# EMGPreamp_extRefv3.net
KiCad netlist of a schematic drawn in EAGLE
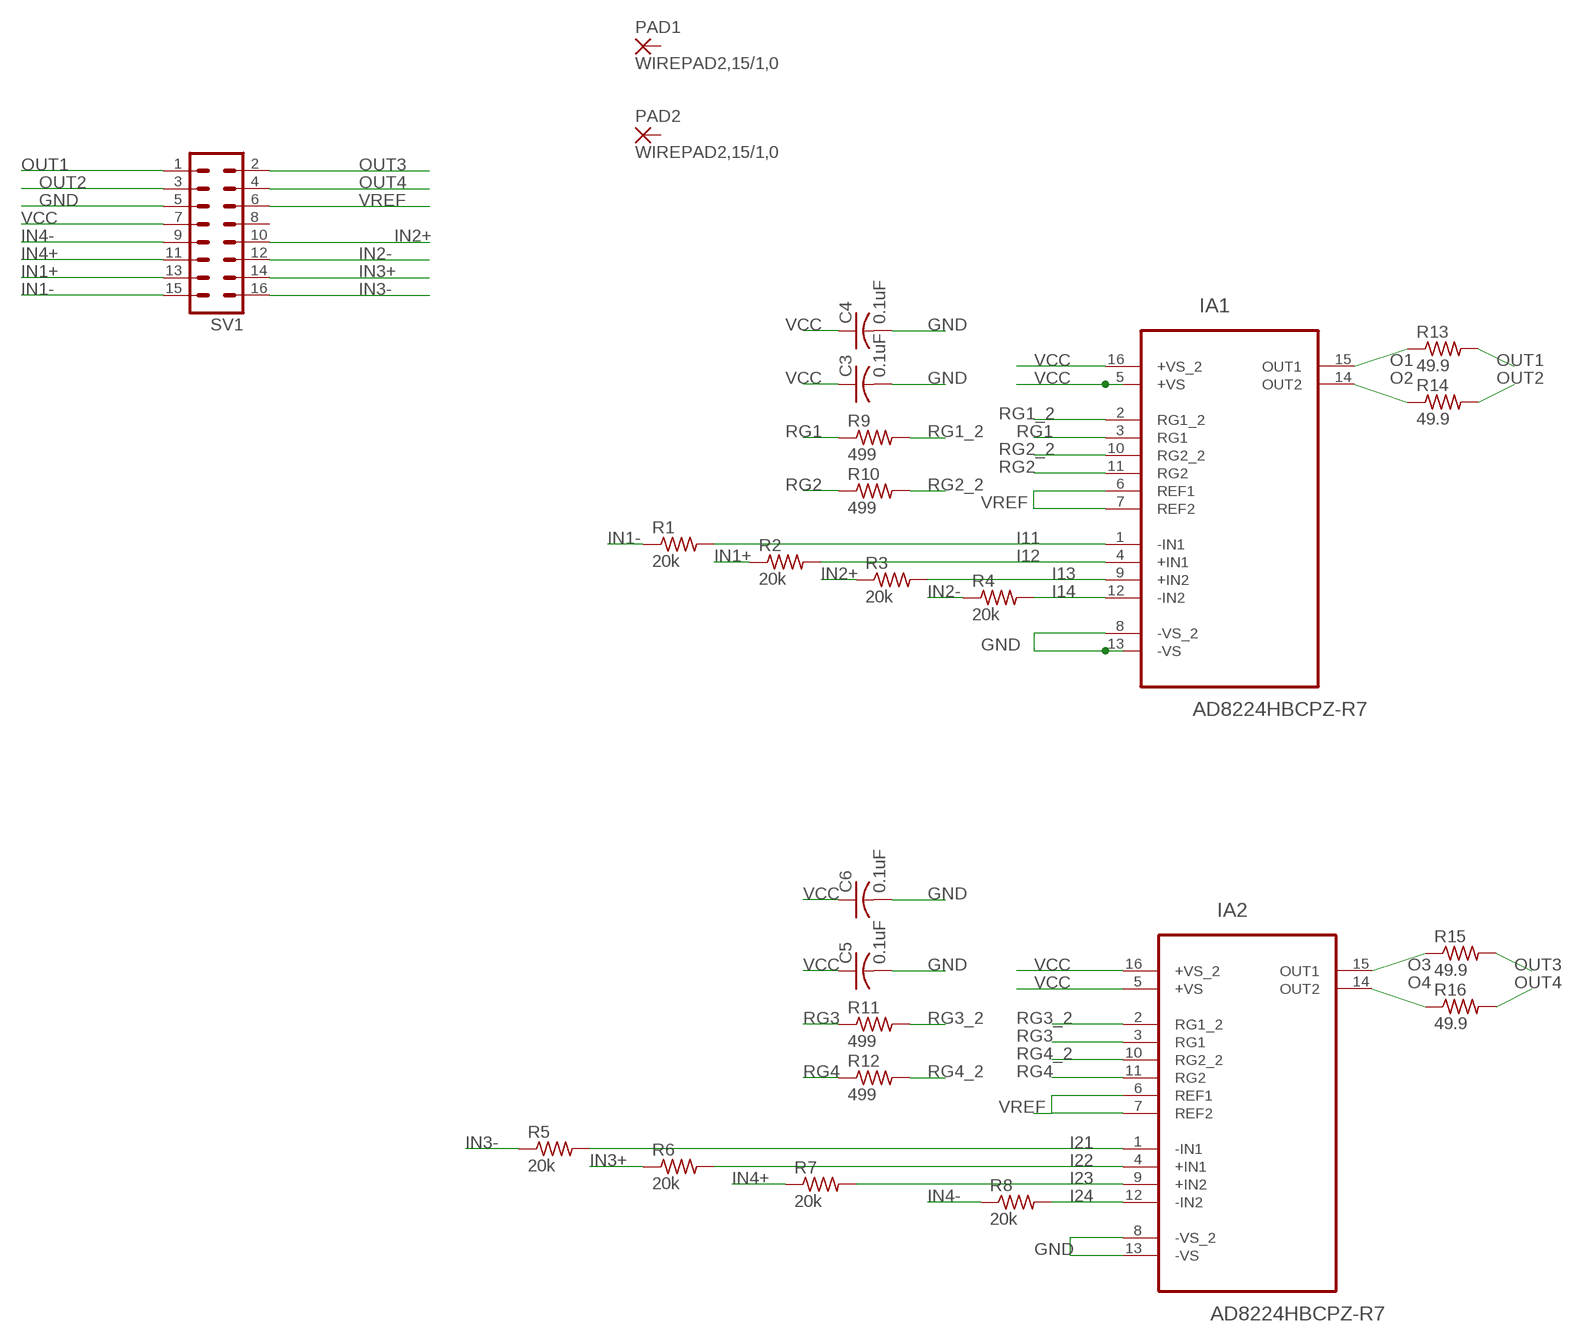
[diagram p0: schematic, sheet 1]

(export (version "E")
  (design (tool "Eeschema 10.0.6"))
  (components
    (comp (ref "C3")
      (value "0.1uF")
      (footprint "eagle-import:C0805")
      (libsource (lib "eagle-import") (part "C-USC0805"))
    )
    (comp (ref "C4")
      (value "0.1uF")
      (footprint "eagle-import:C0805")
      (libsource (lib "eagle-import") (part "C-USC0805"))
    )
    (comp (ref "C5")
      (value "0.1uF")
      (footprint "eagle-import:C0805")
      (libsource (lib "eagle-import") (part "C-USC0805"))
    )
    (comp (ref "C6")
      (value "0.1uF")
      (footprint "eagle-import:C0805")
      (libsource (lib "eagle-import") (part "C-USC0805"))
    )
    (comp (ref "IA1")
      (value "AD8224HBCPZ-R7")
      (footprint "eagle-import:QFN65P400X400X100-16N")
      (libsource (lib "eagle-import") (part "AD8224HBCPZ-R7"))
    )
    (comp (ref "IA2")
      (value "AD8224HBCPZ-R7")
      (footprint "eagle-import:QFN65P400X400X100-16N")
      (libsource (lib "eagle-import") (part "AD8224HBCPZ-R7"))
    )
    (comp (ref "PAD1")
      (value "WIREPAD2,15/1,0")
      (footprint "eagle-import:2,15_1,0")
      (libsource (lib "eagle-import") (part "WIREPAD2,15/1,0"))
    )
    (comp (ref "PAD2")
      (value "WIREPAD2,15/1,0")
      (footprint "eagle-import:2,15_1,0")
      (libsource (lib "eagle-import") (part "WIREPAD2,15/1,0"))
    )
    (comp (ref "R1")
      (value "20k")
      (footprint "eagle-import:R0805")
      (libsource (lib "eagle-import") (part "R-US_R0805"))
    )
    (comp (ref "R2")
      (value "20k")
      (footprint "eagle-import:R0805")
      (libsource (lib "eagle-import") (part "R-US_R0805"))
    )
    (comp (ref "R3")
      (value "20k")
      (footprint "eagle-import:R0805")
      (libsource (lib "eagle-import") (part "R-US_R0805"))
    )
    (comp (ref "R4")
      (value "20k")
      (footprint "eagle-import:R0805")
      (libsource (lib "eagle-import") (part "R-US_R0805"))
    )
    (comp (ref "R5")
      (value "20k")
      (footprint "eagle-import:R0805")
      (libsource (lib "eagle-import") (part "R-US_R0805"))
    )
    (comp (ref "R6")
      (value "20k")
      (footprint "eagle-import:R0805")
      (libsource (lib "eagle-import") (part "R-US_R0805"))
    )
    (comp (ref "R7")
      (value "20k")
      (footprint "eagle-import:R0805")
      (libsource (lib "eagle-import") (part "R-US_R0805"))
    )
    (comp (ref "R8")
      (value "20k")
      (footprint "eagle-import:R0805")
      (libsource (lib "eagle-import") (part "R-US_R0805"))
    )
    (comp (ref "R9")
      (value "499")
      (footprint "eagle-import:R0805")
      (libsource (lib "eagle-import") (part "R-US_R0805"))
    )
    (comp (ref "R10")
      (value "499")
      (footprint "eagle-import:R0805")
      (libsource (lib "eagle-import") (part "R-US_R0805"))
    )
    (comp (ref "R11")
      (value "499")
      (footprint "eagle-import:R0805")
      (libsource (lib "eagle-import") (part "R-US_R0805"))
    )
    (comp (ref "R12")
      (value "499")
      (footprint "eagle-import:R0805")
      (libsource (lib "eagle-import") (part "R-US_R0805"))
    )
    (comp (ref "R13")
      (value "49.9")
      (footprint "eagle-import:R0805")
      (libsource (lib "eagle-import") (part "R-US_R0805"))
    )
    (comp (ref "R14")
      (value "49.9")
      (footprint "eagle-import:R0805")
      (libsource (lib "eagle-import") (part "R-US_R0805"))
    )
    (comp (ref "R15")
      (value "49.9")
      (footprint "eagle-import:R0805")
      (libsource (lib "eagle-import") (part "R-US_R0805"))
    )
    (comp (ref "R16")
      (value "49.9")
      (footprint "eagle-import:R0805")
      (libsource (lib "eagle-import") (part "R-US_R0805"))
    )
    (comp (ref "SV1")
      (value "MA08-2W")
      (footprint "eagle-import:MA08-2W")
      (libsource (lib "eagle-import") (part "MA08-2W"))
    )
  )
  (nets
    (net (code "1") (name "/GND") (class "Default")
      (node (ref "C3") (pin "2") (pinfunction "2_2") (pintype "passive"))
      (node (ref "C4") (pin "2") (pinfunction "2_2") (pintype "passive"))
      (node (ref "C5") (pin "2") (pinfunction "2_2") (pintype "passive"))
      (node (ref "C6") (pin "2") (pinfunction "2_2") (pintype "passive"))
      (node (ref "IA1") (pin "13") (pinfunction "-VS_13") (pintype "power_in"))
      (node (ref "IA1") (pin "8") (pinfunction "-VS_2_8") (pintype "power_in"))
      (node (ref "IA2") (pin "13") (pinfunction "-VS_13") (pintype "power_in"))
      (node (ref "IA2") (pin "8") (pinfunction "-VS_2_8") (pintype "power_in"))
      (node (ref "SV1") (pin "5") (pinfunction "5_5") (pintype "passive"))
    )
    (net (code "2") (name "/I11") (class "Default")
      (node (ref "IA1") (pin "1") (pinfunction "-IN1_1") (pintype "input"))
      (node (ref "R1") (pin "2") (pinfunction "2_2") (pintype "passive"))
    )
    (net (code "3") (name "/I12") (class "Default")
      (node (ref "IA1") (pin "4") (pinfunction "+IN1_4") (pintype "input"))
      (node (ref "R2") (pin "2") (pinfunction "2_2") (pintype "passive"))
    )
    (net (code "4") (name "/I13") (class "Default")
      (node (ref "IA1") (pin "9") (pinfunction "+IN2_9") (pintype "input"))
      (node (ref "R3") (pin "2") (pinfunction "2_2") (pintype "passive"))
    )
    (net (code "5") (name "/I14") (class "Default")
      (node (ref "IA1") (pin "12") (pinfunction "-IN2_12") (pintype "input"))
      (node (ref "R4") (pin "2") (pinfunction "2_2") (pintype "passive"))
    )
    (net (code "6") (name "/I21") (class "Default")
      (node (ref "IA2") (pin "1") (pinfunction "-IN1_1") (pintype "input"))
      (node (ref "R5") (pin "2") (pinfunction "2_2") (pintype "passive"))
    )
    (net (code "7") (name "/I22") (class "Default")
      (node (ref "IA2") (pin "4") (pinfunction "+IN1_4") (pintype "input"))
      (node (ref "R6") (pin "2") (pinfunction "2_2") (pintype "passive"))
    )
    (net (code "8") (name "/I23") (class "Default")
      (node (ref "IA2") (pin "9") (pinfunction "+IN2_9") (pintype "input"))
      (node (ref "R7") (pin "2") (pinfunction "2_2") (pintype "passive"))
    )
    (net (code "9") (name "/I24") (class "Default")
      (node (ref "IA2") (pin "12") (pinfunction "-IN2_12") (pintype "input"))
      (node (ref "R8") (pin "2") (pinfunction "2_2") (pintype "passive"))
    )
    (net (code "10") (name "/IN1+") (class "Default")
      (node (ref "R2") (pin "1") (pinfunction "1_1") (pintype "passive"))
      (node (ref "SV1") (pin "13") (pinfunction "13_13") (pintype "passive"))
    )
    (net (code "11") (name "/IN1-") (class "Default")
      (node (ref "R1") (pin "1") (pinfunction "1_1") (pintype "passive"))
      (node (ref "SV1") (pin "15") (pinfunction "15_15") (pintype "passive"))
    )
    (net (code "12") (name "/IN2+") (class "Default")
      (node (ref "R3") (pin "1") (pinfunction "1_1") (pintype "passive"))
      (node (ref "SV1") (pin "10") (pinfunction "10_10") (pintype "passive"))
    )
    (net (code "13") (name "/IN2-") (class "Default")
      (node (ref "R4") (pin "1") (pinfunction "1_1") (pintype "passive"))
      (node (ref "SV1") (pin "12") (pinfunction "12_12") (pintype "passive"))
    )
    (net (code "14") (name "/IN3+") (class "Default")
      (node (ref "R6") (pin "1") (pinfunction "1_1") (pintype "passive"))
      (node (ref "SV1") (pin "14") (pinfunction "14_14") (pintype "passive"))
    )
    (net (code "15") (name "/IN3-") (class "Default")
      (node (ref "R5") (pin "1") (pinfunction "1_1") (pintype "passive"))
      (node (ref "SV1") (pin "16") (pinfunction "16_16") (pintype "passive"))
    )
    (net (code "16") (name "/IN4+") (class "Default")
      (node (ref "R7") (pin "1") (pinfunction "1_1") (pintype "passive"))
      (node (ref "SV1") (pin "11") (pinfunction "11_11") (pintype "passive"))
    )
    (net (code "17") (name "/IN4-") (class "Default")
      (node (ref "R8") (pin "1") (pinfunction "1_1") (pintype "passive"))
      (node (ref "SV1") (pin "9") (pinfunction "9_9") (pintype "passive"))
    )
    (net (code "18") (name "/O1") (class "Default")
      (node (ref "IA1") (pin "15") (pinfunction "OUT1_15") (pintype "output"))
      (node (ref "R13") (pin "1") (pinfunction "1_1") (pintype "passive"))
    )
    (net (code "19") (name "/O2") (class "Default")
      (node (ref "IA1") (pin "14") (pinfunction "OUT2_14") (pintype "output"))
      (node (ref "R14") (pin "1") (pinfunction "1_1") (pintype "passive"))
    )
    (net (code "20") (name "/O3") (class "Default")
      (node (ref "IA2") (pin "15") (pinfunction "OUT1_15") (pintype "output"))
      (node (ref "R15") (pin "1") (pinfunction "1_1") (pintype "passive"))
    )
    (net (code "21") (name "/O4") (class "Default")
      (node (ref "IA2") (pin "14") (pinfunction "OUT2_14") (pintype "output"))
      (node (ref "R16") (pin "1") (pinfunction "1_1") (pintype "passive"))
    )
    (net (code "22") (name "/OUT1") (class "Default")
      (node (ref "R13") (pin "2") (pinfunction "2_2") (pintype "passive"))
      (node (ref "SV1") (pin "1") (pinfunction "1_1") (pintype "passive"))
    )
    (net (code "23") (name "/OUT2") (class "Default")
      (node (ref "R14") (pin "2") (pinfunction "2_2") (pintype "passive"))
      (node (ref "SV1") (pin "3") (pinfunction "3_3") (pintype "passive"))
    )
    (net (code "24") (name "/OUT3") (class "Default")
      (node (ref "R15") (pin "2") (pinfunction "2_2") (pintype "passive"))
      (node (ref "SV1") (pin "2") (pinfunction "2_2") (pintype "passive"))
    )
    (net (code "25") (name "/OUT4") (class "Default")
      (node (ref "R16") (pin "2") (pinfunction "2_2") (pintype "passive"))
      (node (ref "SV1") (pin "4") (pinfunction "4_4") (pintype "passive"))
    )
    (net (code "26") (name "/RG1") (class "Default")
      (node (ref "IA1") (pin "3") (pinfunction "RG1_3") (pintype "passive"))
      (node (ref "R9") (pin "1") (pinfunction "1_1") (pintype "passive"))
    )
    (net (code "27") (name "/RG1_2") (class "Default")
      (node (ref "IA1") (pin "2") (pinfunction "RG1_2_2") (pintype "passive"))
      (node (ref "R9") (pin "2") (pinfunction "2_2") (pintype "passive"))
    )
    (net (code "28") (name "/RG2") (class "Default")
      (node (ref "IA1") (pin "11") (pinfunction "RG2_11") (pintype "passive"))
      (node (ref "R10") (pin "1") (pinfunction "1_1") (pintype "passive"))
    )
    (net (code "29") (name "/RG2_2") (class "Default")
      (node (ref "IA1") (pin "10") (pinfunction "RG2_2_10") (pintype "passive"))
      (node (ref "R10") (pin "2") (pinfunction "2_2") (pintype "passive"))
    )
    (net (code "30") (name "/RG3") (class "Default")
      (node (ref "IA2") (pin "3") (pinfunction "RG1_3") (pintype "passive"))
      (node (ref "R11") (pin "1") (pinfunction "1_1") (pintype "passive"))
    )
    (net (code "31") (name "/RG3_2") (class "Default")
      (node (ref "IA2") (pin "2") (pinfunction "RG1_2_2") (pintype "passive"))
      (node (ref "R11") (pin "2") (pinfunction "2_2") (pintype "passive"))
    )
    (net (code "32") (name "/RG4") (class "Default")
      (node (ref "IA2") (pin "11") (pinfunction "RG2_11") (pintype "passive"))
      (node (ref "R12") (pin "1") (pinfunction "1_1") (pintype "passive"))
    )
    (net (code "33") (name "/RG4_2") (class "Default")
      (node (ref "IA2") (pin "10") (pinfunction "RG2_2_10") (pintype "passive"))
      (node (ref "R12") (pin "2") (pinfunction "2_2") (pintype "passive"))
    )
    (net (code "34") (name "/VCC") (class "Default")
      (node (ref "C3") (pin "1") (pinfunction "1_1") (pintype "passive"))
      (node (ref "C4") (pin "1") (pinfunction "1_1") (pintype "passive"))
      (node (ref "C5") (pin "1") (pinfunction "1_1") (pintype "passive"))
      (node (ref "C6") (pin "1") (pinfunction "1_1") (pintype "passive"))
      (node (ref "IA1") (pin "16") (pinfunction "+VS_2_16") (pintype "power_in"))
      (node (ref "IA1") (pin "5") (pinfunction "+VS_5") (pintype "power_in"))
      (node (ref "IA2") (pin "16") (pinfunction "+VS_2_16") (pintype "power_in"))
      (node (ref "IA2") (pin "5") (pinfunction "+VS_5") (pintype "power_in"))
      (node (ref "SV1") (pin "7") (pinfunction "7_7") (pintype "passive"))
    )
    (net (code "35") (name "/VREF") (class "Default")
      (node (ref "IA1") (pin "6") (pinfunction "REF1_6") (pintype "input"))
      (node (ref "IA1") (pin "7") (pinfunction "REF2_7") (pintype "input"))
      (node (ref "IA2") (pin "6") (pinfunction "REF1_6") (pintype "input"))
      (node (ref "IA2") (pin "7") (pinfunction "REF2_7") (pintype "input"))
      (node (ref "SV1") (pin "6") (pinfunction "6_6") (pintype "passive"))
    )
    (net (code "36") (name "unconnected-(PAD1-P-Pad1)") (class "Default")
      (node (ref "PAD1") (pin "1") (pinfunction "P_1") (pintype "passive"))
    )
    (net (code "37") (name "unconnected-(PAD2-P-Pad1)") (class "Default")
      (node (ref "PAD2") (pin "1") (pinfunction "P_1") (pintype "passive"))
    )
    (net (code "38") (name "unconnected-(SV1-Pad8)") (class "Default")
      (node (ref "SV1") (pin "8") (pinfunction "8_8") (pintype "passive"))
    )
  )
)
